# AirBee.net
KiCad netlist of a schematic drawn in Altium Designer
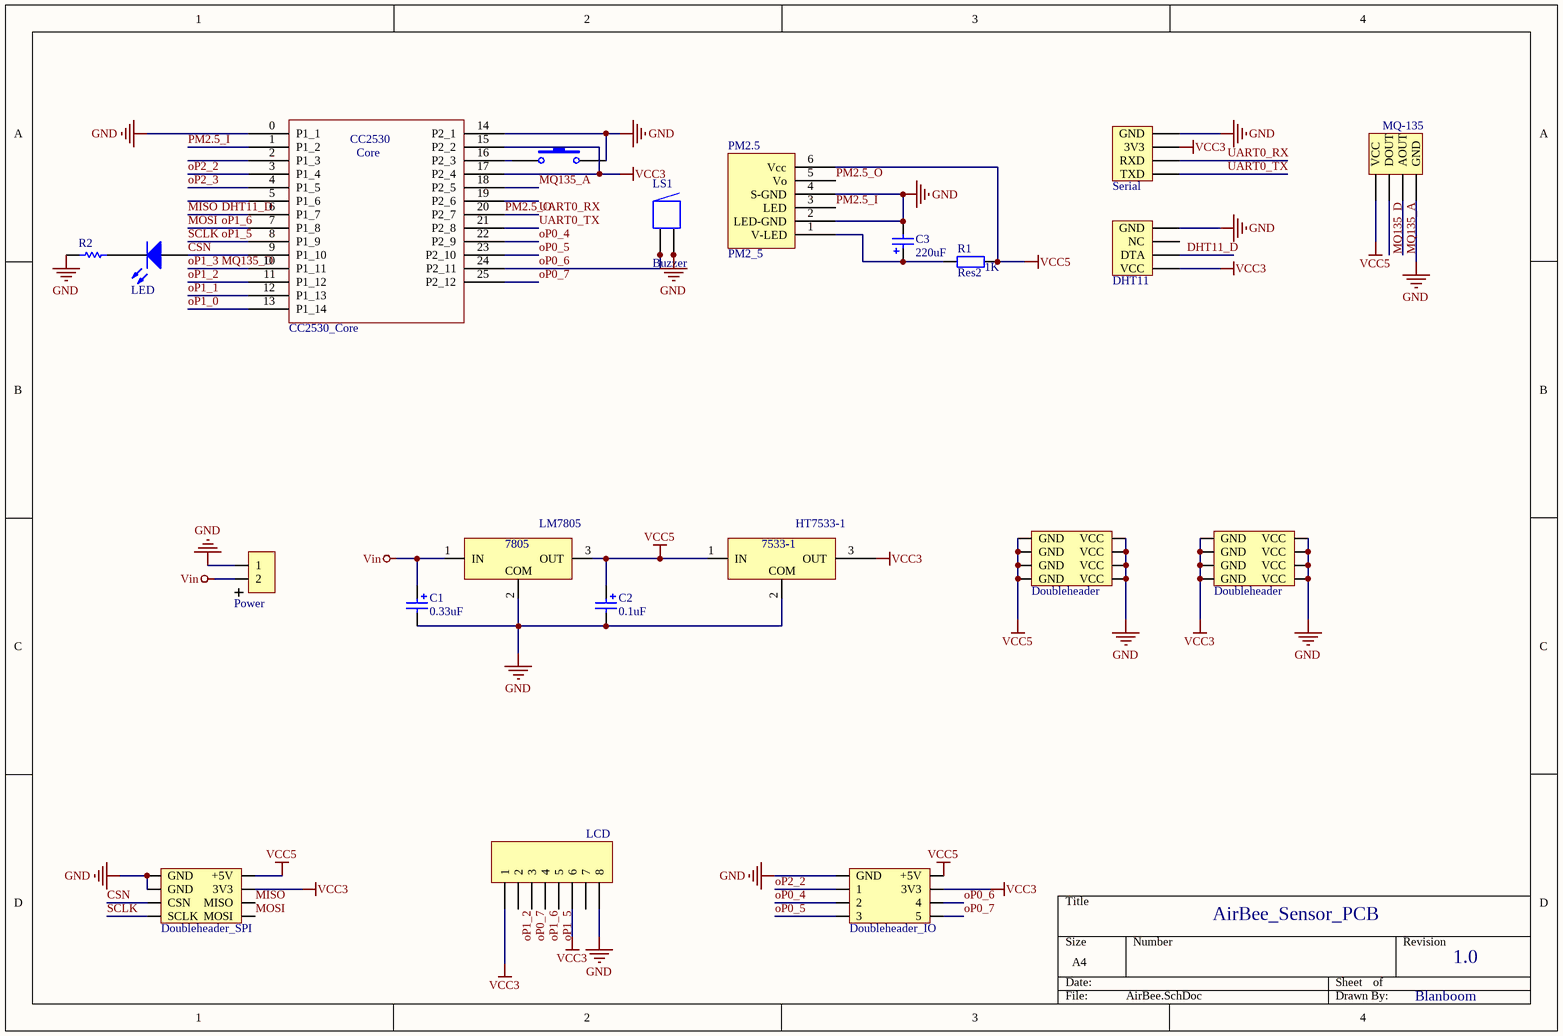
[diagram p0: AirBee.SchDoc]

(export (version "E")
  (design (tool "Eeschema 10.0.6"))
  (components
    (comp (ref "2530")
      (value "CC2530_Core")
      (footprint "CC2530_Core")
      (libsource (lib "AirBee") (part "CC2530_Core"))
    )
    (comp (ref "7533") (value "HT7533-1") (footprint "PNP") (libsource (lib "AirBee") (part "HT7533-1")))
    (comp (ref "7805") (value "LM7805") (footprint "7805") (libsource (lib "AirBee") (part "LM7805")))
    (comp (ref "C1") (value "0.33uF") (footprint "CAP-10uF") (libsource (lib "MyLib") (part "cap")))
    (comp (ref "C2") (value "0.1uF") (footprint "CAP-10uF") (libsource (lib "MyLib") (part "cap")))
    (comp (ref "C3") (value "220uF") (footprint "CAP-100uF") (libsource (lib "MyLib") (part "cap")))
    (comp (ref "D1")
      (value "LED")
      (footprint "LED")
      (description "Typical INFRARED GaAs LED")
      (fields (field (name "PUBLISHER") "Altium Limited"))
      (libsource (lib "Miscellaneous Devices") (part "LED0"))
    )
    (comp (ref "DHT11") (value "DHT11") (footprint "DHT11") (libsource (lib "AirBee") (part "DHT11")))
    (comp (ref "IO2")
      (value "Doubleheader_IO")
      (footprint "header16")
      (libsource (lib "AirBee") (part "Doubleheader_IO"))
    )
    (comp (ref "LCD") (value "HEAder8") (footprint "header8") (libsource (lib "MyLib") (part "HEAder8")))
    (comp (ref "LS1")
      (value "Buzzer")
      (footprint "5V-BUZZER")
      (description "Magnetic Transducer Buzzer")
      (fields (field (name "PUBLISHER") "Altium Limited"))
      (libsource (lib "Miscellaneous Devices") (part "Buzzer"))
    )
    (comp (ref "MQ-135") (value "MQ_135") (footprint "MQ_135") (libsource (lib "AirBee") (part "MQ_135")))
    (comp (ref "PM2.5") (value "PM2_5") (footprint "PM2.5") (libsource (lib "AirBee") (part "PM2_5")))
    (comp (ref "Power") (value "Power") (footprint "dianyuan") (libsource (lib "AirBee") (part "Power")))
    (comp (ref "PWR5V")
      (value "Doubleheader")
      (footprint "header16")
      (libsource (lib "AirBee") (part "Doubleheader"))
    )
    (comp (ref "PWR33")
      (value "Doubleheader")
      (footprint "header16")
      (libsource (lib "AirBee") (part "Doubleheader"))
    )
    (comp (ref "R1")
      (value "Res2")
      (footprint "AXIAL-0.4")
      (description "Resistor")
      (fields (field (name "ALTIUM_VALUE") "1K") (field (name "PUBLISHER") "Altium Limited"))
      (libsource (lib "Miscellaneous Devices") (part "Res2"))
    )
    (comp (ref "R2")
      (value "Res")
      (footprint "AXIAL-0.3")
      (description "Resistor")
      (fields (field (name "PUBLISHER") "Altium Limited"))
      (libsource (lib "Miscellaneous Devices") (part "Res1"))
    )
    (comp (ref "Reset") (value "Switch") (footprint "微动开关") (libsource (lib "AirBee") (part "Switch")))
    (comp (ref "Serial") (value "Serial") (footprint "HEADER4") (libsource (lib "AirBee") (part "Serial")))
    (comp (ref "SPI")
      (value "Doubleheader_SPI")
      (footprint "header16")
      (libsource (lib "AirBee") (part "Doubleheader_SPI"))
    )
  )
  (nets
    (net (code "1") (name "/CSN") (class "Default")
      (node (ref "2530") (pin "9") (pinfunction "P1_10_9") (pintype "passive"))
      (node (ref "D1") (pin "1") (pinfunction "A_1") (pintype "passive"))
      (node (ref "SPI") (pin "3") (pinfunction "CSN_3") (pintype "passive"))
    )
    (net (code "2") (name "/DHT11_D") (class "Default")
      (node (ref "2530") (pin "6") (pinfunction "P1_7_6") (pintype "passive"))
      (node (ref "DHT11") (pin "2") (pinfunction "DTA_2") (pintype "passive"))
      (node (ref "SPI") (pin "6") (pinfunction "MISO_6") (pintype "passive"))
    )
    (net (code "3") (name "/MOSI") (class "Default")
      (node (ref "2530") (pin "7") (pinfunction "P1_8_7") (pintype "passive"))
      (node (ref "LCD") (pin "4") (pinfunction "4_4") (pintype "passive"))
      (node (ref "SPI") (pin "5") (pinfunction "MOSI_5") (pintype "passive"))
    )
    (net (code "4") (name "/MQ135_A") (class "Default")
      (node (ref "2530") (pin "18") (pinfunction "P2_5_18") (pintype "passive"))
      (node (ref "MQ-135") (pin "3") (pinfunction "AOUT_3") (pintype "passive"))
    )
    (net (code "5") (name "/MQ135_D") (class "Default")
      (node (ref "2530") (pin "10") (pinfunction "P1_11_10") (pintype "passive"))
      (node (ref "MQ-135") (pin "2") (pinfunction "DOUT_2") (pintype "passive"))
    )
    (net (code "6") (name "/PM2.5_I") (class "Default")
      (node (ref "2530") (pin "1") (pinfunction "P1_2_1") (pintype "passive"))
      (node (ref "PM2.5") (pin "3") (pinfunction "LED_3") (pintype "passive"))
    )
    (net (code "7") (name "/PM2.5_O") (class "Default")
      (node (ref "2530") (pin "20") (pinfunction "P2_7_20") (pintype "passive"))
      (node (ref "PM2.5") (pin "5") (pinfunction "Vo_5") (pintype "passive"))
      (node (ref "Serial") (pin "2") (pinfunction "RXD_2") (pintype "passive"))
    )
    (net (code "8") (name "/SCLK") (class "Default")
      (node (ref "2530") (pin "8") (pinfunction "P1_9_8") (pintype "passive"))
      (node (ref "LCD") (pin "5") (pinfunction "5_5") (pintype "passive"))
      (node (ref "SPI") (pin "4") (pinfunction "SCLK_4") (pintype "passive"))
    )
    (net (code "9") (name "/UART0_TX") (class "Default")
      (node (ref "2530") (pin "21") (pinfunction "P2_8_21") (pintype "passive"))
      (node (ref "Serial") (pin "1") (pinfunction "TXD_1") (pintype "passive"))
    )
    (net (code "10") (name "/oP0_4") (class "Default")
      (node (ref "2530") (pin "22") (pinfunction "P2_9_22") (pintype "passive"))
      (node (ref "IO2") (pin "3") (pinfunction "2_3") (pintype "passive"))
    )
    (net (code "11") (name "/oP0_5") (class "Default")
      (node (ref "2530") (pin "23") (pinfunction "P2_10_23") (pintype "passive"))
      (node (ref "IO2") (pin "4") (pinfunction "3_4") (pintype "passive"))
    )
    (net (code "12") (name "/oP0_6") (class "Default")
      (node (ref "2530") (pin "24") (pinfunction "P2_11_24") (pintype "passive"))
      (node (ref "IO2") (pin "6") (pinfunction "4_6") (pintype "passive"))
      (node (ref "LS1") (pin "1") (pinfunction "1_1") (pintype "passive"))
      (node (ref "LS1") (pin "1A") (pinfunction "1A_1A") (pintype "passive"))
    )
    (net (code "13") (name "/oP0_7") (class "Default")
      (node (ref "2530") (pin "25") (pinfunction "P2_12_25") (pintype "passive"))
      (node (ref "IO2") (pin "5") (pinfunction "5_5") (pintype "passive"))
      (node (ref "LCD") (pin "3") (pinfunction "3_3") (pintype "passive"))
    )
    (net (code "14") (name "/oP1_0") (class "Default")
      (node (ref "2530") (pin "13") (pinfunction "P1_14_13") (pintype "passive"))
    )
    (net (code "15") (name "/oP1_1") (class "Default")
      (node (ref "2530") (pin "12") (pinfunction "P1_13_12") (pintype "passive"))
    )
    (net (code "16") (name "/oP1_2") (class "Default")
      (node (ref "2530") (pin "11") (pinfunction "P1_12_11") (pintype "passive"))
      (node (ref "LCD") (pin "2") (pinfunction "2_2") (pintype "passive"))
    )
    (net (code "17") (name "/oP2_2") (class "Default")
      (node (ref "2530") (pin "3") (pinfunction "P1_4_3") (pintype "passive"))
      (node (ref "IO2") (pin "2") (pinfunction "1_2") (pintype "passive"))
    )
    (net (code "18") (name "/oP2_3") (class "Default")
      (node (ref "2530") (pin "4") (pinfunction "P1_5_4") (pintype "passive"))
    )
    (net (code "19") (name "GND") (class "Default")
      (node (ref "2530") (pin "0") (pinfunction "P1_1_0") (pintype "passive"))
      (node (ref "2530") (pin "14") (pinfunction "P2_1_14") (pintype "passive"))
      (node (ref "7533") (pin "2") (pinfunction "COM_2") (pintype "passive"))
      (node (ref "7805") (pin "2") (pinfunction "COM_2") (pintype "passive"))
      (node (ref "C1") (pin "2") (pinfunction "2_2") (pintype "passive"))
      (node (ref "C2") (pin "2") (pinfunction "2_2") (pintype "passive"))
      (node (ref "C3") (pin "2") (pinfunction "2_2") (pintype "passive"))
      (node (ref "DHT11") (pin "4") (pinfunction "GND_4") (pintype "passive"))
      (node (ref "IO2") (pin "1") (pinfunction "GND_1") (pintype "passive"))
      (node (ref "LCD") (pin "8") (pinfunction "8_8") (pintype "passive"))
      (node (ref "LS1") (pin "2") (pinfunction "2_2") (pintype "passive"))
      (node (ref "LS1") (pin "2A") (pinfunction "2A_2A") (pintype "passive"))
      (node (ref "MQ-135") (pin "4") (pinfunction "GND_4") (pintype "passive"))
      (node (ref "PM2.5") (pin "2") (pinfunction "LED-GND_2") (pintype "passive"))
      (node (ref "PM2.5") (pin "4") (pinfunction "S-GND_4") (pintype "passive"))
      (node (ref "PWR33") (pin "5") (pinfunction "VCC_5") (pintype "passive"))
      (node (ref "PWR33") (pin "6") (pinfunction "VCC_6") (pintype "passive"))
      (node (ref "PWR33") (pin "7") (pinfunction "VCC_7") (pintype "passive"))
      (node (ref "PWR33") (pin "8") (pinfunction "VCC_8") (pintype "passive"))
      (node (ref "PWR5V") (pin "5") (pinfunction "VCC_5") (pintype "passive"))
      (node (ref "PWR5V") (pin "6") (pinfunction "VCC_6") (pintype "passive"))
      (node (ref "PWR5V") (pin "7") (pinfunction "VCC_7") (pintype "passive"))
      (node (ref "PWR5V") (pin "8") (pinfunction "VCC_8") (pintype "passive"))
      (node (ref "Power") (pin "1") (pinfunction "1_1") (pintype "passive"))
      (node (ref "R2") (pin "1") (pinfunction "1_1") (pintype "passive"))
      (node (ref "Reset") (pin "2") (pinfunction "2_2") (pintype "passive"))
      (node (ref "SPI") (pin "1") (pinfunction "GND_1") (pintype "passive"))
      (node (ref "SPI") (pin "2") (pinfunction "GND_2") (pintype "passive"))
      (node (ref "Serial") (pin "4") (pinfunction "GND_4") (pintype "passive"))
    )
    (net (code "20") (name "Net-(2530-P2_3)") (class "Default")
      (node (ref "2530") (pin "16") (pinfunction "P2_3_16") (pintype "passive"))
      (node (ref "Reset") (pin "1") (pinfunction "1_1") (pintype "passive"))
    )
    (net (code "21") (name "Net-(D1-K)") (class "Default")
      (node (ref "D1") (pin "2") (pinfunction "K_2") (pintype "passive"))
      (node (ref "R2") (pin "2") (pinfunction "2_2") (pintype "passive"))
    )
    (net (code "22") (name "Net-(PM2.5-V-LED)") (class "Default")
      (node (ref "C3") (pin "1") (pinfunction "1_1") (pintype "passive"))
      (node (ref "PM2.5") (pin "1") (pinfunction "V-LED_1") (pintype "passive"))
      (node (ref "R1") (pin "2") (pinfunction "2_2") (pintype "passive"))
    )
    (net (code "23") (name "VCC3") (class "Default")
      (node (ref "2530") (pin "15") (pinfunction "P2_2_15") (pintype "passive"))
      (node (ref "2530") (pin "17") (pinfunction "P2_4_17") (pintype "passive"))
      (node (ref "7533") (pin "3") (pinfunction "OUT_3") (pintype "passive"))
      (node (ref "DHT11") (pin "1") (pinfunction "VCC_1") (pintype "passive"))
      (node (ref "IO2") (pin "7") (pinfunction "3V3_7") (pintype "passive"))
      (node (ref "LCD") (pin "1") (pinfunction "1_1") (pintype "passive"))
      (node (ref "LCD") (pin "6") (pinfunction "6_6") (pintype "passive"))
      (node (ref "PWR33") (pin "1") (pinfunction "GND_1") (pintype "passive"))
      (node (ref "PWR33") (pin "2") (pinfunction "GND_2") (pintype "passive"))
      (node (ref "PWR33") (pin "3") (pinfunction "GND_3") (pintype "passive"))
      (node (ref "PWR33") (pin "4") (pinfunction "GND_4") (pintype "passive"))
      (node (ref "SPI") (pin "7") (pinfunction "3V3_7") (pintype "passive"))
      (node (ref "Serial") (pin "3") (pinfunction "3V3_3") (pintype "passive"))
    )
    (net (code "24") (name "VCC5") (class "Default")
      (node (ref "7533") (pin "1") (pinfunction "IN_1") (pintype "passive"))
      (node (ref "7805") (pin "3") (pinfunction "OUT_3") (pintype "passive"))
      (node (ref "C2") (pin "1") (pinfunction "1_1") (pintype "passive"))
      (node (ref "IO2") (pin "8") (pinfunction "+5V_8") (pintype "passive"))
      (node (ref "MQ-135") (pin "1") (pinfunction "VCC_1") (pintype "passive"))
      (node (ref "PM2.5") (pin "6") (pinfunction "Vcc_6") (pintype "passive"))
      (node (ref "PWR5V") (pin "1") (pinfunction "GND_1") (pintype "passive"))
      (node (ref "PWR5V") (pin "2") (pinfunction "GND_2") (pintype "passive"))
      (node (ref "PWR5V") (pin "3") (pinfunction "GND_3") (pintype "passive"))
      (node (ref "PWR5V") (pin "4") (pinfunction "GND_4") (pintype "passive"))
      (node (ref "R1") (pin "1") (pinfunction "1_1") (pintype "passive"))
      (node (ref "SPI") (pin "8") (pinfunction "+5V_8") (pintype "passive"))
    )
    (net (code "25") (name "Vin") (class "Default")
      (node (ref "7805") (pin "1") (pinfunction "IN_1") (pintype "passive"))
      (node (ref "C1") (pin "1") (pinfunction "1_1") (pintype "passive"))
      (node (ref "Power") (pin "2") (pinfunction "2_2") (pintype "passive"))
    )
    (net (code "26") (name "unconnected-(2530-P1_3-Pad2)") (class "Default")
      (node (ref "2530") (pin "2") (pinfunction "P1_3_2") (pintype "passive"))
    )
    (net (code "27") (name "unconnected-(2530-P1_6-Pad5)") (class "Default")
      (node (ref "2530") (pin "5") (pinfunction "P1_6_5") (pintype "passive"))
    )
    (net (code "28") (name "unconnected-(2530-P2_6-Pad19)") (class "Default")
      (node (ref "2530") (pin "19") (pinfunction "P2_6_19") (pintype "passive"))
    )
    (net (code "29") (name "unconnected-(DHT11-NC-Pad3)") (class "Default")
      (node (ref "DHT11") (pin "3") (pinfunction "NC_3") (pintype "passive"))
    )
    (net (code "30") (name "unconnected-(LCD-Pad7)") (class "Default")
      (node (ref "LCD") (pin "7") (pinfunction "7_7") (pintype "passive"))
    )
  )
)
